# CANMOD-v1_0.net
KiCad netlist of a schematic drawn in EAGLE
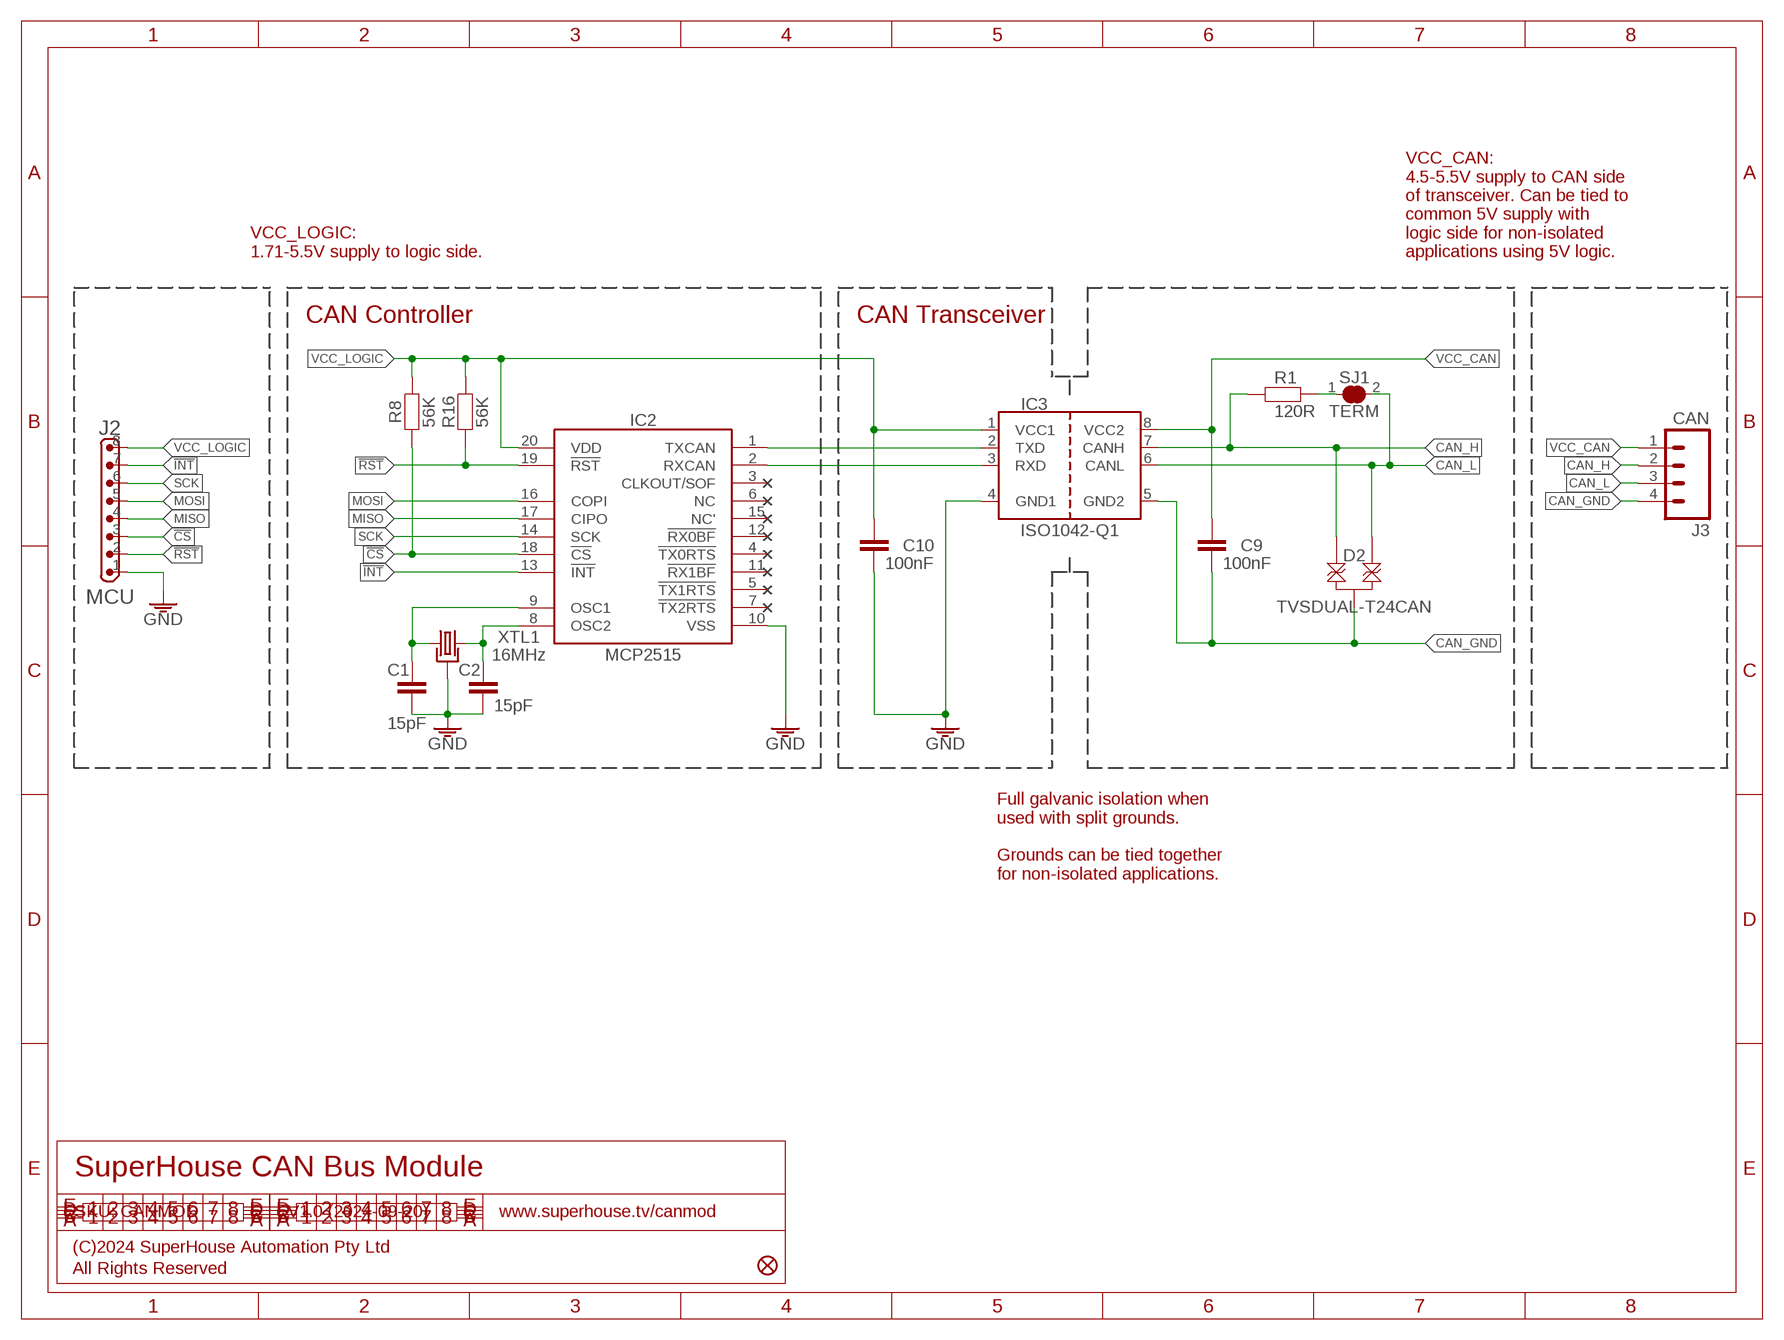
[diagram p0: schematic, sheet 1]

(export (version "E")
  (design (tool "Eeschema 10.0.6"))
  (components
    (comp (ref "C1")
      (value "15pF")
      (footprint "eagle-import:C0603")
      (libsource (lib "eagle-import") (part "CAP0603"))
    )
    (comp (ref "C2")
      (value "15pF")
      (footprint "eagle-import:C0603")
      (libsource (lib "eagle-import") (part "CAP0603"))
    )
    (comp (ref "C9")
      (value "100nF")
      (footprint "eagle-import:C0603")
      (libsource (lib "eagle-import") (part "CAP0603"))
    )
    (comp (ref "C10")
      (value "100nF")
      (footprint "eagle-import:C0603")
      (libsource (lib "eagle-import") (part "CAP0603"))
    )
    (comp (ref "D2")
      (value "TVSDUAL-T24CAN")
      (footprint "eagle-import:SOT23-3")
      (libsource (lib "eagle-import") (part "TVSDUAL-T24CAN"))
    )
    (comp (ref "FID1")
      (value "FIDUCIAL1X2.5")
      (footprint "eagle-import:FIDUCIAL-1X2.5")
      (libsource (lib "eagle-import") (part "FIDUCIAL1X2.5"))
    )
    (comp (ref "IC2")
      (value "SN65HVD231DR")
      (footprint "eagle-import:TSSOP20")
      (libsource (lib "eagle-import") (part "MCP2515"))
    )
    (comp (ref "IC3")
      (value "ISO1042-Q1")
      (footprint "eagle-import:SO08-W")
      (libsource (lib "eagle-import") (part "ISO1042-Q1"))
    )
    (comp (ref "J2")
      (value "MCU")
      (footprint "eagle-import:1X08")
      (libsource (lib "eagle-import") (part "M08-PLAIN"))
    )
    (comp (ref "J3")
      (value "CAN")
      (footprint "eagle-import:1X04")
      (libsource (lib "eagle-import") (part "M04-PLAIN"))
    )
    (comp (ref "R1")
      (value "120R")
      (footprint "eagle-import:R2010")
      (libsource (lib "eagle-import") (part "RESISTOR2010"))
    )
    (comp (ref "R8")
      (value "56K")
      (footprint "eagle-import:R0603")
      (libsource (lib "eagle-import") (part "RESISTOR0603"))
    )
    (comp (ref "R16")
      (value "56K")
      (footprint "eagle-import:R0603")
      (libsource (lib "eagle-import") (part "RESISTOR0603"))
    )
    (comp (ref "SJ1")
      (value "TERM")
      (footprint "eagle-import:SJC")
      (libsource (lib "eagle-import") (part "SJC-NORMAL"))
    )
    (comp (ref "XTL1")
      (value "16MHz")
      (footprint "eagle-import:CRYSTAL-SMD-3X2")
      (libsource (lib "eagle-import") (part "CRYSTAL-GND3X2"))
    )
  )
  (nets
    (net (code "1") (name "/~{CS}") (class "Default")
      (node (ref "IC2") (pin "18") (pinfunction "~{CS}_18") (pintype "bidirectional"))
      (node (ref "J2") (pin "3") (pinfunction "3_3") (pintype "passive"))
      (node (ref "R8") (pin "1") (pinfunction "1_1") (pintype "passive"))
    )
    (net (code "2") (name "/~{INT}") (class "Default")
      (node (ref "IC2") (pin "13") (pinfunction "~{INT}_13") (pintype "bidirectional"))
      (node (ref "J2") (pin "7") (pinfunction "7_7") (pintype "passive"))
    )
    (net (code "3") (name "/~{RST}") (class "Default")
      (node (ref "IC2") (pin "19") (pinfunction "~{RST}_19") (pintype "bidirectional"))
      (node (ref "J2") (pin "2") (pinfunction "2_2") (pintype "passive"))
      (node (ref "R16") (pin "1") (pinfunction "1_1") (pintype "passive"))
    )
    (net (code "4") (name "CAN_GND") (class "Default")
      (node (ref "C9") (pin "2") (pinfunction "2_2") (pintype "passive"))
      (node (ref "D2") (pin "3") (pinfunction "3_3") (pintype "passive"))
      (node (ref "IC3") (pin "5") (pinfunction "GND2_5") (pintype "bidirectional"))
      (node (ref "J3") (pin "4") (pinfunction "4_4") (pintype "passive"))
    )
    (net (code "5") (name "CAN_H") (class "Default")
      (node (ref "D2") (pin "2") (pinfunction "2_2") (pintype "passive"))
      (node (ref "IC3") (pin "7") (pinfunction "CANH_7") (pintype "bidirectional"))
      (node (ref "J3") (pin "2") (pinfunction "2_2") (pintype "passive"))
      (node (ref "R1") (pin "1") (pinfunction "1_1") (pintype "passive"))
    )
    (net (code "6") (name "CAN_L") (class "Default")
      (node (ref "D2") (pin "1") (pinfunction "1_1") (pintype "passive"))
      (node (ref "IC3") (pin "6") (pinfunction "CANL_6") (pintype "bidirectional"))
      (node (ref "J3") (pin "3") (pinfunction "3_3") (pintype "passive"))
      (node (ref "SJ1") (pin "2") (pinfunction "2_2") (pintype "passive"))
    )
    (net (code "7") (name "GND") (class "Default")
      (node (ref "C1") (pin "2") (pinfunction "2_2") (pintype "passive"))
      (node (ref "C10") (pin "2") (pinfunction "2_2") (pintype "passive"))
      (node (ref "C2") (pin "2") (pinfunction "2_2") (pintype "passive"))
      (node (ref "IC2") (pin "10") (pinfunction "VSS_10") (pintype "bidirectional"))
      (node (ref "IC3") (pin "4") (pinfunction "GND1_4") (pintype "bidirectional"))
      (node (ref "J2") (pin "1") (pinfunction "1_1") (pintype "passive"))
      (node (ref "XTL1") (pin "2") (pinfunction "GND_2") (pintype "bidirectional"))
      (node (ref "XTL1") (pin "4") (pinfunction "GND_4") (pintype "bidirectional"))
    )
    (net (code "8") (name "MISO") (class "Default")
      (node (ref "IC2") (pin "17") (pinfunction "CIPO_17") (pintype "bidirectional"))
      (node (ref "J2") (pin "4") (pinfunction "4_4") (pintype "passive"))
    )
    (net (code "9") (name "MOSI") (class "Default")
      (node (ref "IC2") (pin "16") (pinfunction "COPI_16") (pintype "bidirectional"))
      (node (ref "J2") (pin "5") (pinfunction "5_5") (pintype "passive"))
    )
    (net (code "10") (name "Net-(IC2-OSC1)") (class "Default")
      (node (ref "C1") (pin "1") (pinfunction "1_1") (pintype "passive"))
      (node (ref "IC2") (pin "9") (pinfunction "OSC1_9") (pintype "bidirectional"))
      (node (ref "XTL1") (pin "1") (pinfunction "1_1") (pintype "passive"))
    )
    (net (code "11") (name "Net-(IC2-OSC2)") (class "Default")
      (node (ref "C2") (pin "1") (pinfunction "1_1") (pintype "passive"))
      (node (ref "IC2") (pin "8") (pinfunction "OSC2_8") (pintype "bidirectional"))
      (node (ref "XTL1") (pin "3") (pinfunction "2_3") (pintype "passive"))
    )
    (net (code "12") (name "Net-(IC2-RXCAN)") (class "Default")
      (node (ref "IC2") (pin "2") (pinfunction "RXCAN_2") (pintype "bidirectional"))
      (node (ref "IC3") (pin "3") (pinfunction "RXD_3") (pintype "bidirectional"))
    )
    (net (code "13") (name "Net-(IC2-TXCAN)") (class "Default")
      (node (ref "IC2") (pin "1") (pinfunction "TXCAN_1") (pintype "bidirectional"))
      (node (ref "IC3") (pin "2") (pinfunction "TXD_2") (pintype "bidirectional"))
    )
    (net (code "14") (name "Net-(R1-Pad2)") (class "Default")
      (node (ref "R1") (pin "2") (pinfunction "2_2") (pintype "passive"))
      (node (ref "SJ1") (pin "1") (pinfunction "1_1") (pintype "passive"))
    )
    (net (code "15") (name "SCK") (class "Default")
      (node (ref "IC2") (pin "14") (pinfunction "SCK_14") (pintype "bidirectional"))
      (node (ref "J2") (pin "6") (pinfunction "6_6") (pintype "passive"))
    )
    (net (code "16") (name "VCC_CAN") (class "Default")
      (node (ref "C9") (pin "1") (pinfunction "1_1") (pintype "passive"))
      (node (ref "IC3") (pin "8") (pinfunction "VCC2_8") (pintype "bidirectional"))
      (node (ref "J3") (pin "1") (pinfunction "1_1") (pintype "passive"))
    )
    (net (code "17") (name "VCC_LOGIC") (class "Default")
      (node (ref "C10") (pin "1") (pinfunction "1_1") (pintype "passive"))
      (node (ref "IC2") (pin "20") (pinfunction "VDD_20") (pintype "bidirectional"))
      (node (ref "IC3") (pin "1") (pinfunction "VCC1_1") (pintype "bidirectional"))
      (node (ref "J2") (pin "8") (pinfunction "8_8") (pintype "passive"))
      (node (ref "R16") (pin "2") (pinfunction "2_2") (pintype "passive"))
      (node (ref "R8") (pin "2") (pinfunction "2_2") (pintype "passive"))
    )
    (net (code "18") (name "unconnected-(IC2-CLKOUT{slash}SOF-Pad3)") (class "Default")
      (node (ref "IC2") (pin "3") (pinfunction "CLKOUT/SOF_3") (pintype "bidirectional"))
    )
    (net (code "19") (name "unconnected-(IC2-NC'-Pad15)") (class "Default")
      (node (ref "IC2") (pin "15") (pinfunction "NC'_15") (pintype "bidirectional"))
    )
    (net (code "20") (name "unconnected-(IC2-NC-Pad6)") (class "Default")
      (node (ref "IC2") (pin "6") (pinfunction "NC_6") (pintype "bidirectional"))
    )
    (net (code "21") (name "unconnected-(IC2-~{RX0BF}-Pad12)") (class "Default")
      (node (ref "IC2") (pin "12") (pinfunction "~{RX0BF}_12") (pintype "bidirectional"))
    )
    (net (code "22") (name "unconnected-(IC2-~{RX1BF}-Pad11)") (class "Default")
      (node (ref "IC2") (pin "11") (pinfunction "~{RX1BF}_11") (pintype "bidirectional"))
    )
    (net (code "23") (name "unconnected-(IC2-~{TX0RTS}-Pad4)") (class "Default")
      (node (ref "IC2") (pin "4") (pinfunction "~{TX0RTS}_4") (pintype "bidirectional"))
    )
    (net (code "24") (name "unconnected-(IC2-~{TX1RTS}-Pad5)") (class "Default")
      (node (ref "IC2") (pin "5") (pinfunction "~{TX1RTS}_5") (pintype "bidirectional"))
    )
    (net (code "25") (name "unconnected-(IC2-~{TX2RTS}-Pad7)") (class "Default")
      (node (ref "IC2") (pin "7") (pinfunction "~{TX2RTS}_7") (pintype "bidirectional"))
    )
  )
)
